# usbxlater.net
KiCad netlist of a schematic drawn in EAGLE
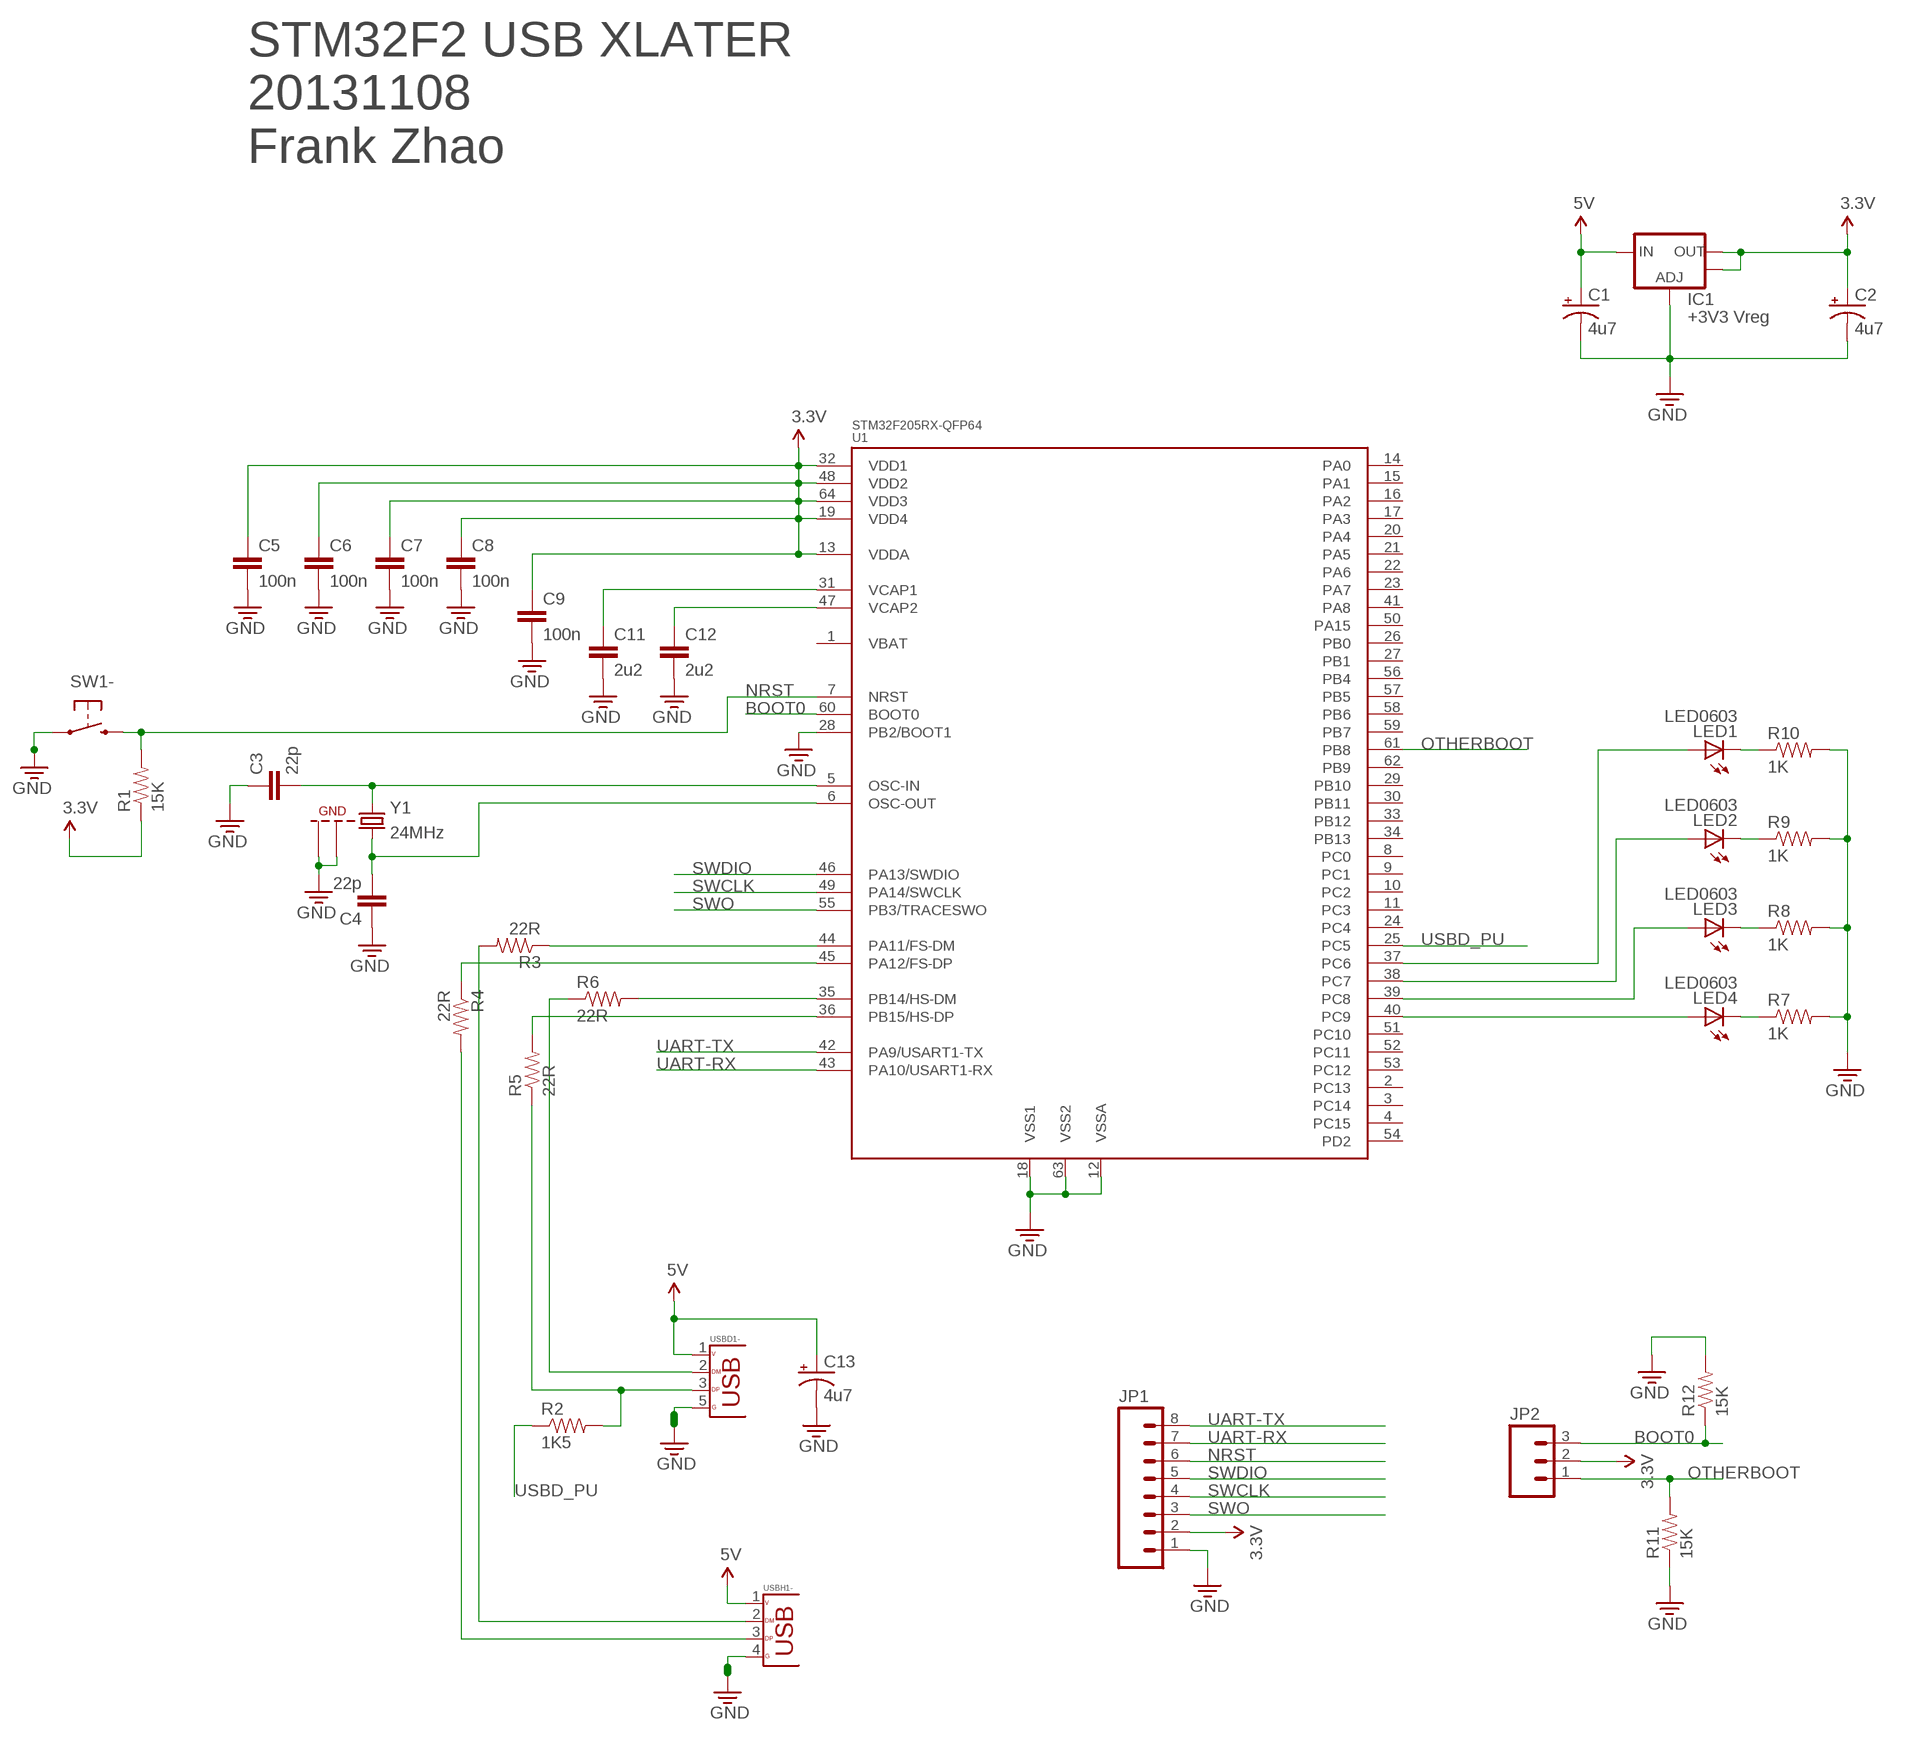
[diagram p0: schematic, sheet 1]

(export (version "E")
  (design (tool "Eeschema 10.0.6"))
  (components
    (comp (ref "C1")
      (value "4u7")
      (footprint "eagle-import:EIA3216")
      (libsource (lib "eagle-import") (part "CAP_POL1206"))
    )
    (comp (ref "C2")
      (value "4u7")
      (footprint "eagle-import:EIA3216")
      (libsource (lib "eagle-import") (part "CAP_POL1206"))
    )
    (comp (ref "C3")
      (value "22p")
      (footprint "eagle-import:0603-CAP-NOLEAK")
      (libsource (lib "eagle-import") (part "CAP0603-CAP-NOLEAK"))
    )
    (comp (ref "C4")
      (value "22p")
      (footprint "eagle-import:0603-CAP-NOLEAK")
      (libsource (lib "eagle-import") (part "CAP0603-CAP-NOLEAK"))
    )
    (comp (ref "C5")
      (value "100n")
      (footprint "eagle-import:0603-CAP-NOLEAK")
      (libsource (lib "eagle-import") (part "CAP0603-CAP-NOLEAK"))
    )
    (comp (ref "C6")
      (value "100n")
      (footprint "eagle-import:0603-CAP-NOLEAK")
      (libsource (lib "eagle-import") (part "CAP0603-CAP-NOLEAK"))
    )
    (comp (ref "C7")
      (value "100n")
      (footprint "eagle-import:0603-CAP-NOLEAK")
      (libsource (lib "eagle-import") (part "CAP0603-CAP-NOLEAK"))
    )
    (comp (ref "C8")
      (value "100n")
      (footprint "eagle-import:0603-CAP-NOLEAK")
      (libsource (lib "eagle-import") (part "CAP0603-CAP-NOLEAK"))
    )
    (comp (ref "C9")
      (value "100n")
      (footprint "eagle-import:0603-CAP-NOLEAK")
      (libsource (lib "eagle-import") (part "CAP0603-CAP-NOLEAK"))
    )
    (comp (ref "C11")
      (value "2u2")
      (footprint "eagle-import:0603-CAP-NOLEAK")
      (libsource (lib "eagle-import") (part "CAP0603-CAP-NOLEAK"))
    )
    (comp (ref "C12")
      (value "2u2")
      (footprint "eagle-import:0603-CAP-NOLEAK")
      (libsource (lib "eagle-import") (part "CAP0603-CAP-NOLEAK"))
    )
    (comp (ref "C13")
      (value "4u7")
      (footprint "eagle-import:EIA3216")
      (libsource (lib "eagle-import") (part "CAP_POL1206"))
    )
    (comp (ref "IC1")
      (value "+3V3 Vreg")
      (footprint "eagle-import:SOT223")
      (libsource (lib "eagle-import") (part "V_REG_LM1117SOT223"))
    )
    (comp (ref "JP1")
      (value "M081X08")
      (footprint "eagle-import:1X08")
      (libsource (lib "eagle-import") (part "M081X08"))
    )
    (comp (ref "JP2")
      (value "M03PTH")
      (footprint "eagle-import:1X03")
      (libsource (lib "eagle-import") (part "M03PTH"))
    )
    (comp (ref "LED1")
      (value "LED0603")
      (footprint "eagle-import:LED-0603")
      (libsource (lib "eagle-import") (part "LED0603"))
    )
    (comp (ref "LED2")
      (value "LED0603")
      (footprint "eagle-import:LED-0603")
      (libsource (lib "eagle-import") (part "LED0603"))
    )
    (comp (ref "LED3")
      (value "LED0603")
      (footprint "eagle-import:LED-0603")
      (libsource (lib "eagle-import") (part "LED0603"))
    )
    (comp (ref "LED4")
      (value "LED0603")
      (footprint "eagle-import:LED-0603")
      (libsource (lib "eagle-import") (part "LED0603"))
    )
    (comp (ref "R1")
      (value "15K")
      (footprint "eagle-import:0603-RES")
      (libsource (lib "eagle-import") (part "RESISTOR0603-RES"))
    )
    (comp (ref "R2")
      (value "1K5")
      (footprint "eagle-import:0603-RES")
      (libsource (lib "eagle-import") (part "RESISTOR0603-RES"))
    )
    (comp (ref "R3")
      (value "22R")
      (footprint "eagle-import:0603-RES")
      (libsource (lib "eagle-import") (part "RESISTOR0603-RES"))
    )
    (comp (ref "R4")
      (value "22R")
      (footprint "eagle-import:0603-RES")
      (libsource (lib "eagle-import") (part "RESISTOR0603-RES"))
    )
    (comp (ref "R5")
      (value "22R")
      (footprint "eagle-import:0603-RES")
      (libsource (lib "eagle-import") (part "RESISTOR0603-RES"))
    )
    (comp (ref "R6")
      (value "22R")
      (footprint "eagle-import:0603-RES")
      (libsource (lib "eagle-import") (part "RESISTOR0603-RES"))
    )
    (comp (ref "R7")
      (value "1K")
      (footprint "eagle-import:0603-RES-NOLEAK")
      (libsource (lib "eagle-import") (part "RESISTOR0603-RES-NOLEAK"))
    )
    (comp (ref "R8")
      (value "1K")
      (footprint "eagle-import:0603-RES")
      (libsource (lib "eagle-import") (part "RESISTOR0603-RES"))
    )
    (comp (ref "R9")
      (value "1K")
      (footprint "eagle-import:0603-RES-NOLEAK")
      (libsource (lib "eagle-import") (part "RESISTOR0603-RES-NOLEAK"))
    )
    (comp (ref "R10")
      (value "1K")
      (footprint "eagle-import:0603-RES")
      (libsource (lib "eagle-import") (part "RESISTOR0603-RES"))
    )
    (comp (ref "R11")
      (value "15K")
      (footprint "eagle-import:0603-RES-NOLEAK")
      (libsource (lib "eagle-import") (part "RESISTOR0603-RES-NOLEAK"))
    )
    (comp (ref "R12")
      (value "15K")
      (footprint "eagle-import:0603-RES-NOLEAK")
      (libsource (lib "eagle-import") (part "RESISTOR0603-RES-NOLEAK"))
    )
    (comp (ref "SW1")
      (value "SWITCH-B3U-1100-BOSS")
      (footprint "eagle-import:SWITCH-TACT-B3U-1100P-B")
      (libsource (lib "eagle-import") (part "SWITCH-B3U-1100-BOSS"))
    )
    (comp (ref "U1")
      (value "STM32F205RX-QFP64")
      (footprint "eagle-import:TQFP64")
      (libsource (lib "eagle-import") (part "STM32F205RX-QFP64"))
    )
    (comp (ref "USBD1")
      (value "USB-6S-MICRO_B")
      (footprint "eagle-import:USB_MICRO_B")
      (libsource (lib "eagle-import") (part "USB-6S-MICRO_B"))
    )
    (comp (ref "USBH1")
      (value "USB-A-RV")
      (footprint "eagle-import:USB-A-RV")
      (libsource (lib "eagle-import") (part "USB-A-RV"))
    )
    (comp (ref "Y1")
      (value "24MHz")
      (footprint "eagle-import:CRYSTAL-SMD-3.2X2.5")
      (libsource (lib "eagle-import") (part "CRYSTAL_SMD_GND-3.2X2.5"))
    )
  )
  (nets
    (net (code "1") (name "/BOOT0") (class "Default")
      (node (ref "JP2") (pin "3") (pinfunction "3_3") (pintype "passive"))
      (node (ref "R12") (pin "1") (pinfunction "1_1") (pintype "passive"))
      (node (ref "U1") (pin "60") (pinfunction "BOOT0_60") (pintype "input"))
    )
    (net (code "2") (name "/NRST") (class "Default")
      (node (ref "JP1") (pin "6") (pinfunction "6_6") (pintype "passive"))
      (node (ref "R1") (pin "2") (pinfunction "2_2") (pintype "passive"))
      (node (ref "SW1") (pin "2") (pinfunction "2_2") (pintype "passive"))
      (node (ref "U1") (pin "7") (pinfunction "NRST_7") (pintype "input"))
    )
    (net (code "3") (name "/OTHERBOOT") (class "Default")
      (node (ref "JP2") (pin "1") (pinfunction "1_1") (pintype "passive"))
      (node (ref "R11") (pin "2") (pinfunction "2_2") (pintype "passive"))
      (node (ref "U1") (pin "61") (pinfunction "PB8_61") (pintype "bidirectional"))
    )
    (net (code "4") (name "/SWCLK") (class "Default")
      (node (ref "JP1") (pin "4") (pinfunction "4_4") (pintype "passive"))
      (node (ref "U1") (pin "49") (pinfunction "PA14/SWCLK_49") (pintype "bidirectional"))
    )
    (net (code "5") (name "/SWDIO") (class "Default")
      (node (ref "JP1") (pin "5") (pinfunction "5_5") (pintype "passive"))
      (node (ref "U1") (pin "46") (pinfunction "PA13/SWDIO_46") (pintype "bidirectional"))
    )
    (net (code "6") (name "/SWO") (class "Default")
      (node (ref "JP1") (pin "3") (pinfunction "3_3") (pintype "passive"))
      (node (ref "U1") (pin "55") (pinfunction "PB3/TRACESWO_55") (pintype "bidirectional"))
    )
    (net (code "7") (name "/UART-RX") (class "Default")
      (node (ref "JP1") (pin "7") (pinfunction "7_7") (pintype "passive"))
      (node (ref "U1") (pin "43") (pinfunction "PA10/USART1-RX_43") (pintype "bidirectional"))
    )
    (net (code "8") (name "/UART-TX") (class "Default")
      (node (ref "JP1") (pin "8") (pinfunction "8_8") (pintype "passive"))
      (node (ref "U1") (pin "42") (pinfunction "PA9/USART1-TX_42") (pintype "bidirectional"))
    )
    (net (code "9") (name "/USBD_PU") (class "Default")
      (node (ref "R2") (pin "1") (pinfunction "1_1") (pintype "passive"))
      (node (ref "U1") (pin "25") (pinfunction "PC5_25") (pintype "bidirectional"))
    )
    (net (code "10") (name "3.3V") (class "Default")
      (node (ref "C2") (pin "A") (pinfunction "+_A") (pintype "passive"))
      (node (ref "C5") (pin "1") (pinfunction "1_1") (pintype "passive"))
      (node (ref "C6") (pin "1") (pinfunction "1_1") (pintype "passive"))
      (node (ref "C7") (pin "1") (pinfunction "1_1") (pintype "passive"))
      (node (ref "C8") (pin "1") (pinfunction "1_1") (pintype "passive"))
      (node (ref "C9") (pin "1") (pinfunction "1_1") (pintype "passive"))
      (node (ref "IC1") (pin "2") (pinfunction "OUT_2") (pintype "output"))
      (node (ref "IC1") (pin "4") (pinfunction "OUT_4") (pintype "output"))
      (node (ref "JP1") (pin "2") (pinfunction "2_2") (pintype "passive"))
      (node (ref "JP2") (pin "2") (pinfunction "2_2") (pintype "passive"))
      (node (ref "R1") (pin "1") (pinfunction "1_1") (pintype "passive"))
      (node (ref "U1") (pin "13") (pinfunction "VDDA_13") (pintype "bidirectional"))
      (node (ref "U1") (pin "19") (pinfunction "VDD4_19") (pintype "bidirectional"))
      (node (ref "U1") (pin "32") (pinfunction "VDD1_32") (pintype "bidirectional"))
      (node (ref "U1") (pin "48") (pinfunction "VDD2_48") (pintype "bidirectional"))
      (node (ref "U1") (pin "64") (pinfunction "VDD3_64") (pintype "bidirectional"))
    )
    (net (code "11") (name "5V") (class "Default")
      (node (ref "C1") (pin "A") (pinfunction "+_A") (pintype "passive"))
      (node (ref "C13") (pin "A") (pinfunction "+_A") (pintype "passive"))
      (node (ref "IC1") (pin "3") (pinfunction "IN_3") (pintype "input"))
      (node (ref "USBD1") (pin "1") (pinfunction "VBUS_1") (pintype "bidirectional"))
      (node (ref "USBH1") (pin "1") (pinfunction "VBUS_1") (pintype "bidirectional"))
    )
    (net (code "12") (name "GND") (class "Default")
      (node (ref "C1") (pin "C") (pinfunction "-_C") (pintype "passive"))
      (node (ref "C11") (pin "2") (pinfunction "2_2") (pintype "passive"))
      (node (ref "C12") (pin "2") (pinfunction "2_2") (pintype "passive"))
      (node (ref "C13") (pin "C") (pinfunction "-_C") (pintype "passive"))
      (node (ref "C2") (pin "C") (pinfunction "-_C") (pintype "passive"))
      (node (ref "C3") (pin "1") (pinfunction "1_1") (pintype "passive"))
      (node (ref "C4") (pin "1") (pinfunction "1_1") (pintype "passive"))
      (node (ref "C5") (pin "2") (pinfunction "2_2") (pintype "passive"))
      (node (ref "C6") (pin "2") (pinfunction "2_2") (pintype "passive"))
      (node (ref "C7") (pin "2") (pinfunction "2_2") (pintype "passive"))
      (node (ref "C8") (pin "2") (pinfunction "2_2") (pintype "passive"))
      (node (ref "C9") (pin "2") (pinfunction "2_2") (pintype "passive"))
      (node (ref "IC1") (pin "1") (pinfunction "ADJ_1") (pintype "input"))
      (node (ref "JP1") (pin "1") (pinfunction "1_1") (pintype "passive"))
      (node (ref "R10") (pin "2") (pinfunction "2_2") (pintype "passive"))
      (node (ref "R11") (pin "1") (pinfunction "1_1") (pintype "passive"))
      (node (ref "R12") (pin "2") (pinfunction "2_2") (pintype "passive"))
      (node (ref "R7") (pin "2") (pinfunction "2_2") (pintype "passive"))
      (node (ref "R8") (pin "2") (pinfunction "2_2") (pintype "passive"))
      (node (ref "R9") (pin "2") (pinfunction "2_2") (pintype "passive"))
      (node (ref "SW1") (pin "1") (pinfunction "1_1") (pintype "passive"))
      (node (ref "SW1") (pin "BOSS") (pinfunction "P$1_BOSS") (pintype "bidirectional"))
      (node (ref "U1") (pin "12") (pinfunction "VSSA_12") (pintype "bidirectional"))
      (node (ref "U1") (pin "18") (pinfunction "VSS1_18") (pintype "bidirectional"))
      (node (ref "U1") (pin "28") (pinfunction "PB2/BOOT1_28") (pintype "bidirectional"))
      (node (ref "U1") (pin "63") (pinfunction "VSS2_63") (pintype "bidirectional"))
      (node (ref "USBD1") (pin "5") (pinfunction "GND_5") (pintype "bidirectional"))
      (node (ref "USBD1") (pin "P$1") (pinfunction "P$1_P$1") (pintype "bidirectional"))
      (node (ref "USBD1") (pin "P$2") (pinfunction "P$1_P$2") (pintype "bidirectional"))
      (node (ref "USBD1") (pin "P$3") (pinfunction "P$1_P$3") (pintype "bidirectional"))
      (node (ref "USBD1") (pin "P$4") (pinfunction "P$1_P$4") (pintype "bidirectional"))
      (node (ref "USBD1") (pin "S1") (pinfunction "P$1_S1") (pintype "bidirectional"))
      (node (ref "USBD1") (pin "S2") (pinfunction "P$1_S2") (pintype "bidirectional"))
      (node (ref "USBH1") (pin "4") (pinfunction "GND_4") (pintype "bidirectional"))
      (node (ref "USBH1") (pin "S1") (pinfunction "P$1_S1") (pintype "bidirectional"))
      (node (ref "USBH1") (pin "S2") (pinfunction "P$1_S2") (pintype "bidirectional"))
      (node (ref "USBH1") (pin "S3") (pinfunction "P$1_S3") (pintype "bidirectional"))
      (node (ref "USBH1") (pin "S4") (pinfunction "P$1_S4") (pintype "bidirectional"))
      (node (ref "Y1") (pin "2") (pinfunction "GND1_2") (pintype "bidirectional"))
      (node (ref "Y1") (pin "4") (pinfunction "GND2_4") (pintype "bidirectional"))
    )
    (net (code "13") (name "Net-(LED1-PadC)") (class "Default")
      (node (ref "LED1") (pin "C") (pinfunction "C_C") (pintype "passive"))
      (node (ref "R10") (pin "1") (pinfunction "1_1") (pintype "passive"))
    )
    (net (code "14") (name "Net-(LED2-PadC)") (class "Default")
      (node (ref "LED2") (pin "C") (pinfunction "C_C") (pintype "passive"))
      (node (ref "R9") (pin "1") (pinfunction "1_1") (pintype "passive"))
    )
    (net (code "15") (name "Net-(LED3-PadC)") (class "Default")
      (node (ref "LED3") (pin "C") (pinfunction "C_C") (pintype "passive"))
      (node (ref "R8") (pin "1") (pinfunction "1_1") (pintype "passive"))
    )
    (net (code "16") (name "Net-(LED4-PadC)") (class "Default")
      (node (ref "LED4") (pin "C") (pinfunction "C_C") (pintype "passive"))
      (node (ref "R7") (pin "1") (pinfunction "1_1") (pintype "passive"))
    )
    (net (code "17") (name "Net-(U1-OSC-IN)") (class "Default")
      (node (ref "C3") (pin "2") (pinfunction "2_2") (pintype "passive"))
      (node (ref "U1") (pin "5") (pinfunction "OSC-IN_5") (pintype "bidirectional"))
      (node (ref "Y1") (pin "1") (pinfunction "1_1") (pintype "passive"))
    )
    (net (code "18") (name "Net-(U1-OSC-OUT)") (class "Default")
      (node (ref "C4") (pin "2") (pinfunction "2_2") (pintype "passive"))
      (node (ref "U1") (pin "6") (pinfunction "OSC-OUT_6") (pintype "bidirectional"))
      (node (ref "Y1") (pin "3") (pinfunction "2_3") (pintype "passive"))
    )
    (net (code "19") (name "Net-(U1-PA11{slash}FS-DM)") (class "Default")
      (node (ref "R3") (pin "1") (pinfunction "1_1") (pintype "passive"))
      (node (ref "U1") (pin "44") (pinfunction "PA11/FS-DM_44") (pintype "bidirectional"))
    )
    (net (code "20") (name "Net-(U1-PA12{slash}FS-DP)") (class "Default")
      (node (ref "R4") (pin "1") (pinfunction "1_1") (pintype "passive"))
      (node (ref "U1") (pin "45") (pinfunction "PA12/FS-DP_45") (pintype "bidirectional"))
    )
    (net (code "21") (name "Net-(U1-PB14{slash}HS-DM)") (class "Default")
      (node (ref "R6") (pin "2") (pinfunction "2_2") (pintype "passive"))
      (node (ref "U1") (pin "35") (pinfunction "PB14/HS-DM_35") (pintype "bidirectional"))
    )
    (net (code "22") (name "Net-(U1-PB15{slash}HS-DP)") (class "Default")
      (node (ref "R5") (pin "2") (pinfunction "2_2") (pintype "passive"))
      (node (ref "U1") (pin "36") (pinfunction "PB15/HS-DP_36") (pintype "bidirectional"))
    )
    (net (code "23") (name "Net-(U1-PC6)") (class "Default")
      (node (ref "LED1") (pin "A") (pinfunction "A_A") (pintype "passive"))
      (node (ref "U1") (pin "37") (pinfunction "PC6_37") (pintype "bidirectional"))
    )
    (net (code "24") (name "Net-(U1-PC7)") (class "Default")
      (node (ref "LED2") (pin "A") (pinfunction "A_A") (pintype "passive"))
      (node (ref "U1") (pin "38") (pinfunction "PC7_38") (pintype "bidirectional"))
    )
    (net (code "25") (name "Net-(U1-PC8)") (class "Default")
      (node (ref "LED3") (pin "A") (pinfunction "A_A") (pintype "passive"))
      (node (ref "U1") (pin "39") (pinfunction "PC8_39") (pintype "bidirectional"))
    )
    (net (code "26") (name "Net-(U1-PC9)") (class "Default")
      (node (ref "LED4") (pin "A") (pinfunction "A_A") (pintype "passive"))
      (node (ref "U1") (pin "40") (pinfunction "PC9_40") (pintype "bidirectional"))
    )
    (net (code "27") (name "Net-(U1-VCAP1)") (class "Default")
      (node (ref "C11") (pin "1") (pinfunction "1_1") (pintype "passive"))
      (node (ref "U1") (pin "31") (pinfunction "VCAP1_31") (pintype "bidirectional"))
    )
    (net (code "28") (name "Net-(U1-VCAP2)") (class "Default")
      (node (ref "C12") (pin "1") (pinfunction "1_1") (pintype "passive"))
      (node (ref "U1") (pin "47") (pinfunction "VCAP2_47") (pintype "bidirectional"))
    )
    (net (code "29") (name "Net-(USBD1A-D+)") (class "Default")
      (node (ref "R2") (pin "2") (pinfunction "2_2") (pintype "passive"))
      (node (ref "R5") (pin "1") (pinfunction "1_1") (pintype "passive"))
      (node (ref "USBD1") (pin "3") (pinfunction "D+_3") (pintype "bidirectional"))
    )
    (net (code "30") (name "Net-(USBD1A-D-)") (class "Default")
      (node (ref "R6") (pin "1") (pinfunction "1_1") (pintype "passive"))
      (node (ref "USBD1") (pin "2") (pinfunction "D-_2") (pintype "bidirectional"))
    )
    (net (code "31") (name "Net-(USBH1A-D+)") (class "Default")
      (node (ref "R4") (pin "2") (pinfunction "2_2") (pintype "passive"))
      (node (ref "USBH1") (pin "3") (pinfunction "D+_3") (pintype "bidirectional"))
    )
    (net (code "32") (name "Net-(USBH1A-D-)") (class "Default")
      (node (ref "R3") (pin "2") (pinfunction "2_2") (pintype "passive"))
      (node (ref "USBH1") (pin "2") (pinfunction "D-_2") (pintype "bidirectional"))
    )
    (net (code "33") (name "unconnected-(U1-PA0-Pad14)") (class "Default")
      (node (ref "U1") (pin "14") (pinfunction "PA0_14") (pintype "bidirectional"))
    )
    (net (code "34") (name "unconnected-(U1-PA1-Pad15)") (class "Default")
      (node (ref "U1") (pin "15") (pinfunction "PA1_15") (pintype "bidirectional"))
    )
    (net (code "35") (name "unconnected-(U1-PA2-Pad16)") (class "Default")
      (node (ref "U1") (pin "16") (pinfunction "PA2_16") (pintype "bidirectional"))
    )
    (net (code "36") (name "unconnected-(U1-PA3-Pad17)") (class "Default")
      (node (ref "U1") (pin "17") (pinfunction "PA3_17") (pintype "bidirectional"))
    )
    (net (code "37") (name "unconnected-(U1-PA4-Pad20)") (class "Default")
      (node (ref "U1") (pin "20") (pinfunction "PA4_20") (pintype "bidirectional"))
    )
    (net (code "38") (name "unconnected-(U1-PA5-Pad21)") (class "Default")
      (node (ref "U1") (pin "21") (pinfunction "PA5_21") (pintype "bidirectional"))
    )
    (net (code "39") (name "unconnected-(U1-PA6-Pad22)") (class "Default")
      (node (ref "U1") (pin "22") (pinfunction "PA6_22") (pintype "bidirectional"))
    )
    (net (code "40") (name "unconnected-(U1-PA7-Pad23)") (class "Default")
      (node (ref "U1") (pin "23") (pinfunction "PA7_23") (pintype "bidirectional"))
    )
    (net (code "41") (name "unconnected-(U1-PA8-Pad41)") (class "Default")
      (node (ref "U1") (pin "41") (pinfunction "PA8_41") (pintype "bidirectional"))
    )
    (net (code "42") (name "unconnected-(U1-PA15-Pad50)") (class "Default")
      (node (ref "U1") (pin "50") (pinfunction "PA15_50") (pintype "bidirectional"))
    )
    (net (code "43") (name "unconnected-(U1-PB0-Pad26)") (class "Default")
      (node (ref "U1") (pin "26") (pinfunction "PB0_26") (pintype "bidirectional"))
    )
    (net (code "44") (name "unconnected-(U1-PB1-Pad27)") (class "Default")
      (node (ref "U1") (pin "27") (pinfunction "PB1_27") (pintype "bidirectional"))
    )
    (net (code "45") (name "unconnected-(U1-PB4-Pad56)") (class "Default")
      (node (ref "U1") (pin "56") (pinfunction "PB4_56") (pintype "bidirectional"))
    )
    (net (code "46") (name "unconnected-(U1-PB5-Pad57)") (class "Default")
      (node (ref "U1") (pin "57") (pinfunction "PB5_57") (pintype "bidirectional"))
    )
    (net (code "47") (name "unconnected-(U1-PB6-Pad58)") (class "Default")
      (node (ref "U1") (pin "58") (pinfunction "PB6_58") (pintype "bidirectional"))
    )
    (net (code "48") (name "unconnected-(U1-PB7-Pad59)") (class "Default")
      (node (ref "U1") (pin "59") (pinfunction "PB7_59") (pintype "bidirectional"))
    )
    (net (code "49") (name "unconnected-(U1-PB9-Pad62)") (class "Default")
      (node (ref "U1") (pin "62") (pinfunction "PB9_62") (pintype "bidirectional"))
    )
    (net (code "50") (name "unconnected-(U1-PB10-Pad29)") (class "Default")
      (node (ref "U1") (pin "29") (pinfunction "PB10_29") (pintype "bidirectional"))
    )
    (net (code "51") (name "unconnected-(U1-PB11-Pad30)") (class "Default")
      (node (ref "U1") (pin "30") (pinfunction "PB11_30") (pintype "bidirectional"))
    )
    (net (code "52") (name "unconnected-(U1-PB12-Pad33)") (class "Default")
      (node (ref "U1") (pin "33") (pinfunction "PB12_33") (pintype "bidirectional"))
    )
    (net (code "53") (name "unconnected-(U1-PB13-Pad34)") (class "Default")
      (node (ref "U1") (pin "34") (pinfunction "PB13_34") (pintype "bidirectional"))
    )
    (net (code "54") (name "unconnected-(U1-PC0-Pad8)") (class "Default")
      (node (ref "U1") (pin "8") (pinfunction "PC0_8") (pintype "bidirectional"))
    )
    (net (code "55") (name "unconnected-(U1-PC1-Pad9)") (class "Default")
      (node (ref "U1") (pin "9") (pinfunction "PC1_9") (pintype "bidirectional"))
    )
    (net (code "56") (name "unconnected-(U1-PC2-Pad10)") (class "Default")
      (node (ref "U1") (pin "10") (pinfunction "PC2_10") (pintype "bidirectional"))
    )
    (net (code "57") (name "unconnected-(U1-PC3-Pad11)") (class "Default")
      (node (ref "U1") (pin "11") (pinfunction "PC3_11") (pintype "bidirectional"))
    )
    (net (code "58") (name "unconnected-(U1-PC4-Pad24)") (class "Default")
      (node (ref "U1") (pin "24") (pinfunction "PC4_24") (pintype "bidirectional"))
    )
    (net (code "59") (name "unconnected-(U1-PC10-Pad51)") (class "Default")
      (node (ref "U1") (pin "51") (pinfunction "PC10_51") (pintype "bidirectional"))
    )
    (net (code "60") (name "unconnected-(U1-PC11-Pad52)") (class "Default")
      (node (ref "U1") (pin "52") (pinfunction "PC11_52") (pintype "bidirectional"))
    )
    (net (code "61") (name "unconnected-(U1-PC12-Pad53)") (class "Default")
      (node (ref "U1") (pin "53") (pinfunction "PC12_53") (pintype "bidirectional"))
    )
    (net (code "62") (name "unconnected-(U1-PC13-Pad2)") (class "Default")
      (node (ref "U1") (pin "2") (pinfunction "PC13_2") (pintype "bidirectional"))
    )
    (net (code "63") (name "unconnected-(U1-PC14-Pad3)") (class "Default")
      (node (ref "U1") (pin "3") (pinfunction "PC14_3") (pintype "bidirectional"))
    )
    (net (code "64") (name "unconnected-(U1-PC15-Pad4)") (class "Default")
      (node (ref "U1") (pin "4") (pinfunction "PC15_4") (pintype "bidirectional"))
    )
    (net (code "65") (name "unconnected-(U1-PD2-Pad54)") (class "Default")
      (node (ref "U1") (pin "54") (pinfunction "PD2_54") (pintype "bidirectional"))
    )
    (net (code "66") (name "unconnected-(U1-VBAT-Pad1)") (class "Default")
      (node (ref "U1") (pin "1") (pinfunction "VBAT_1") (pintype "input"))
    )
  )
)
